# 405RGT6.net
KiCad netlist of a schematic drawn in Altium Designer
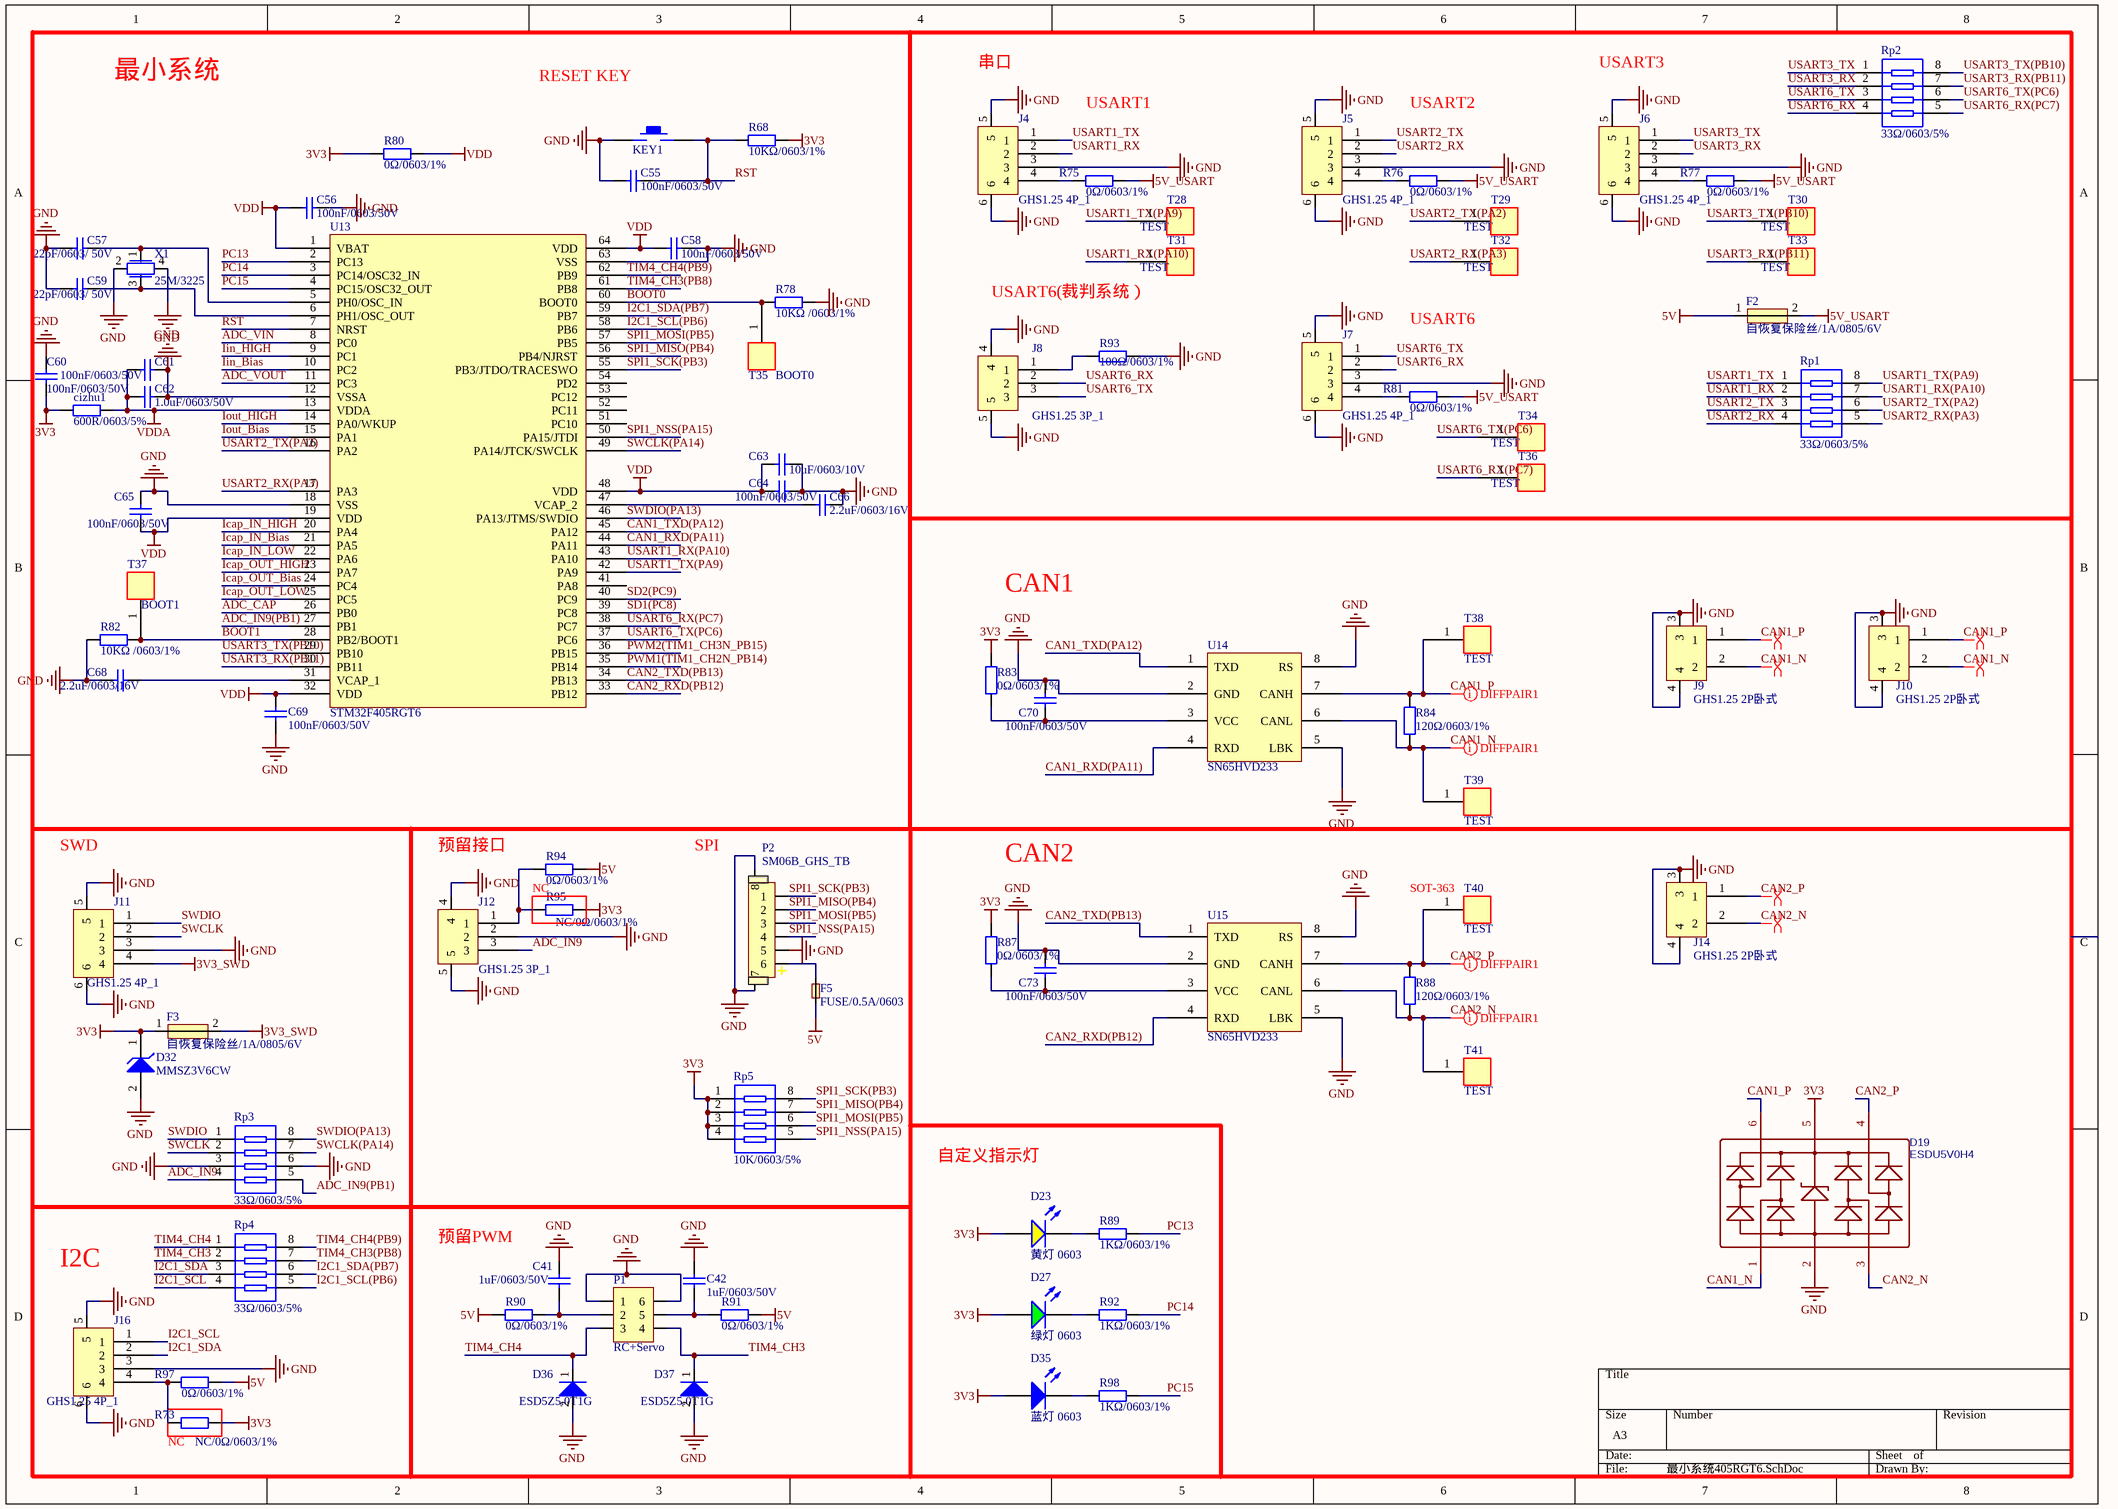
[diagram p0: 最小系统405RGT6.SchDoc]

(export (version "E")
  (design (tool "Eeschema 10.0.6"))
  (components
    (comp (ref "C41")
      (value "1uF/0603/50V")
      (footprint "0603_C")
      (description "贴片电容")
      (libsource (lib "Miscellaneous Devices LC") (part "0603 1uF (105) 10% 50V"))
    )
    (comp (ref "C42")
      (value "1uF/0603/50V")
      (footprint "0603_C")
      (description "贴片电容")
      (libsource (lib "Miscellaneous Devices LC") (part "0603 1uF (105) 10% 50V"))
    )
    (comp (ref "C55")
      (value "100nF/0603/50V")
      (footprint "0603_C")
      (description "贴片电容")
      (libsource (lib "Miscellaneous Devices LC") (part "0603 100nF (104) 10% 50V"))
    )
    (comp (ref "C56")
      (value "100nF/0603/50V")
      (footprint "0603_C")
      (description "贴片电容")
      (libsource (lib "Miscellaneous Devices LC") (part "0603 100nF (104) 10% 50V"))
    )
    (comp (ref "C57")
      (value "22pF/0603/ 50V")
      (footprint "0603_C")
      (description "贴片电容")
      (libsource (lib "Miscellaneous Devices LC") (part "0603 22pF (220) 5% 50V"))
    )
    (comp (ref "C58")
      (value "100nF/0603/50V")
      (footprint "0603_C")
      (description "贴片电容")
      (libsource (lib "Miscellaneous Devices LC") (part "0603 100nF (104) 10% 50V"))
    )
    (comp (ref "C59")
      (value "22pF/0603/ 50V")
      (footprint "0603_C")
      (description "贴片电容")
      (libsource (lib "Miscellaneous Devices LC") (part "0603 22pF (220) 5% 50V"))
    )
    (comp (ref "C60")
      (value "100nF/0603/50V")
      (footprint "0603_C")
      (description "贴片电容")
      (libsource (lib "Miscellaneous Devices LC") (part "0603 100nF (104) 10% 50V"))
    )
    (comp (ref "C61")
      (value "100nF/0603/50V")
      (footprint "0603_C")
      (description "贴片电容")
      (libsource (lib "Miscellaneous Devices LC") (part "0603 100nF (104) 10% 50V"))
    )
    (comp (ref "C62")
      (value "1.0uF/0603/50V")
      (footprint "0603_C")
      (description "贴片电容")
      (libsource (lib "Miscellaneous Devices LC") (part "0603 100nF (104) 10% 50V"))
    )
    (comp (ref "C63")
      (value "10uF/0603/10V")
      (footprint "0603_C")
      (description "贴片电容")
      (libsource (lib "Miscellaneous Devices LC") (part "0603 10uF (106) 10% 10V"))
    )
    (comp (ref "C64")
      (value "100nF/0603/50V")
      (footprint "0603_C")
      (description "贴片电容")
      (libsource (lib "Miscellaneous Devices LC") (part "0603 100nF (104) 10% 50V"))
    )
    (comp (ref "C65")
      (value "100nF/0603/50V")
      (footprint "0603_C")
      (description "贴片电容")
      (libsource (lib "Miscellaneous Devices LC") (part "0603 100nF (104) 10% 50V"))
    )
    (comp (ref "C66")
      (value "2.2uF/0603/16V")
      (footprint "0603_C")
      (description "贴片电容")
      (libsource (lib "Miscellaneous Devices LC") (part "0603 2.2uF (225) 10% 16V"))
    )
    (comp (ref "C68")
      (value "2.2uF/0603/16V")
      (footprint "0603_C")
      (description "贴片电容")
      (libsource (lib "Miscellaneous Devices LC") (part "0603 2.2uF (225) 10% 16V"))
    )
    (comp (ref "C69")
      (value "100nF/0603/50V")
      (footprint "0603_C")
      (description "贴片电容")
      (libsource (lib "Miscellaneous Devices LC") (part "0603 100nF (104) 10% 50V"))
    )
    (comp (ref "C70")
      (value "100nF/0603/50V")
      (footprint "0603_C")
      (description "贴片电容")
      (libsource (lib "Miscellaneous Devices LC") (part "0603 100nF (104) 10% 50V"))
    )
    (comp (ref "C73")
      (value "100nF/0603/50V")
      (footprint "0603_C")
      (description "贴片电容")
      (libsource (lib "Miscellaneous Devices LC") (part "0603 100nF (104) 10% 50V"))
    )
    (comp (ref "cizhu1")
      (value "600R/0603/5%")
      (footprint "0603_R")
      (description "贴片电阻")
      (libsource (lib "Miscellaneous Devices LC") (part "0603 100Ω (1000) 1%"))
    )
    (comp (ref "D19")
      (value "ESDU5V0H4")
      (footprint "SOT-23-6_L2.9-W1.6-P0.95-LS2.8-BR")
      (description "ESD")
      (fields (field (name "BOM_SUPPLIER PART") "C84837"))
      (libsource (lib "数字电源") (part "ESDU5V0H4"))
    )
    (comp (ref "D23")
      (value "黄灯 0603")
      (footprint "0603_LED_S1")
      (description "发光二极管")
      (libsource (lib "Miscellaneous Devices LC") (part "0603 黄灯"))
    )
    (comp (ref "D27")
      (value "绿灯 0603")
      (footprint "0603_LED_S1")
      (description "发光二极管")
      (libsource (lib "Miscellaneous Devices LC") (part "0603 绿灯"))
    )
    (comp (ref "D32")
      (value "MMSZ3V6CW")
      (footprint "SOD-123")
      (description "稳压二极管")
      (libsource (lib "数字电源") (part "LL-34 ZMM3V3"))
    )
    (comp (ref "D35")
      (value "蓝灯 0603")
      (footprint "0603_LED_S1")
      (description "发光二极管")
      (libsource (lib "Miscellaneous Devices LC") (part "0603 蓝灯"))
    )
    (comp (ref "D36")
      (value "ESD5Z5.0T1G")
      (footprint "SOD-523")
      (description "单向TVS")
      (libsource (lib "数字电源") (part "TVS_SOD-523"))
    )
    (comp (ref "D37")
      (value "ESD5Z5.0T1G")
      (footprint "SOD-523")
      (description "单向TVS")
      (libsource (lib "数字电源") (part "TVS_SOD-523"))
    )
    (comp (ref "F2")
      (value "自恢复保险丝/1A/0805/6V")
      (footprint "RobotLab_Common_Used:0805_R")
      (libsource (lib "RobotLab_Common_Used") (part "FUSE/0805"))
    )
    (comp (ref "F3")
      (value "自恢复保险丝/1A/0805/6V")
      (footprint "RobotLab_Common_Used:0805_R")
      (libsource (lib "RobotLab_Common_Used") (part "FUSE/0805"))
    )
    (comp (ref "F5")
      (value "FUSE/0.5A/0603")
      (footprint "0.5A/0603")
      (description "FUSE")
      (libsource (lib "数字电源") (part "FUSE/0.5A/0603"))
    )
    (comp (ref "J4")
      (value "GHS1.25 4P_1")
      (footprint "RobotLab_Common_Used:SM04B-GHS卧式")
      (description "卧式短边")
      (libsource (lib "RobotLab_Common_Used") (part "GHS1.25 4P_1"))
    )
    (comp (ref "J5")
      (value "GHS1.25 4P_1")
      (footprint "RobotLab_Common_Used:SM04B-GHS卧式")
      (description "卧式短边")
      (libsource (lib "RobotLab_Common_Used") (part "GHS1.25 4P_1"))
    )
    (comp (ref "J6")
      (value "GHS1.25 4P_1")
      (footprint "RobotLab_Common_Used:SM04B-GHS卧式")
      (description "卧式短边")
      (libsource (lib "RobotLab_Common_Used") (part "GHS1.25 4P_1"))
    )
    (comp (ref "J7")
      (value "GHS1.25 4P_1")
      (footprint "RobotLab_Common_Used:SM04B-GHS卧式")
      (description "卧式短边")
      (libsource (lib "RobotLab_Common_Used") (part "GHS1.25 4P_1"))
    )
    (comp (ref "J8")
      (value "GHS1.25 3P_1")
      (footprint "RobotLab_Common_Used:SM03B_GHS卧式")
      (description "卧式")
      (libsource (lib "RobotLab_Common_Used") (part "GHS1.25 3P_1"))
    )
    (comp (ref "J9")
      (value "GHS1.25 2P卧式")
      (footprint "RobotLab_Common_Used:SM02B-GHS卧式")
      (description "卧式")
      (libsource (lib "RobotLab_Common_Used") (part "GHS1.25 2P_1"))
    )
    (comp (ref "J10")
      (value "GHS1.25 2P卧式")
      (footprint "RobotLab_Common_Used:SM02B-GHS卧式")
      (description "卧式")
      (libsource (lib "RobotLab_Common_Used") (part "GHS1.25 2P_1"))
    )
    (comp (ref "J11")
      (value "GHS1.25 4P_1")
      (footprint "RobotLab_Common_Used:SM04B-GHS卧式")
      (description "卧式短边")
      (libsource (lib "RobotLab_Common_Used") (part "GHS1.25 4P_1"))
    )
    (comp (ref "J12")
      (value "GHS1.25 3P_1")
      (footprint "RobotLab_Common_Used:SM03B_GHS卧式")
      (description "卧式")
      (libsource (lib "RobotLab_Common_Used") (part "GHS1.25 3P_1"))
    )
    (comp (ref "J14")
      (value "GHS1.25 2P卧式")
      (footprint "RobotLab_Common_Used:SM02B-GHS卧式")
      (description "卧式")
      (libsource (lib "RobotLab_Common_Used") (part "GHS1.25 2P_1"))
    )
    (comp (ref "J16")
      (value "GHS1.25 4P_1")
      (footprint "RobotLab_Common_Used:SM04B-GHS卧式")
      (description "卧式短边")
      (libsource (lib "RobotLab_Common_Used") (part "GHS1.25 4P_1"))
    )
    (comp (ref "KEY1")
      (value "KEY")
      (footprint "RobotLab_Common_Used:SW-SMD1")
      (description "开关")
      (libsource (lib "RobotLab_Common_Used") (part "KEY"))
    )
    (comp (ref "P1") (value "RC+Servo") (footprint "RC+Servo") (libsource (lib "数字电源") (part "DBUS+Servo")))
    (comp (ref "P2")
      (value "SM06B_GHS_TB")
      (footprint "SM06B-GHS-TB")
      (libsource (lib "数字电源") (part "SM06B_GHS_TB"))
    )
    (comp (ref "R68")
      (value "10KΩ/0603/1%")
      (footprint "0603_R")
      (description "贴片电阻")
      (libsource (lib "Miscellaneous Devices LC") (part "0603 10KΩ (1002) 1%"))
    )
    (comp (ref "R73")
      (value "NC/0Ω/0603/1%")
      (footprint "0603_R")
      (description "贴片电阻")
      (libsource (lib "") (part "0603 0Ω (0R0) 1%_1"))
    )
    (comp (ref "R75")
      (value "0Ω/0603/1%")
      (footprint "0603_R")
      (description "贴片电阻")
      (libsource (lib "") (part "0603 0Ω (0R0) 1%_1"))
    )
    (comp (ref "R76")
      (value "0Ω/0603/1%")
      (footprint "0603_R")
      (description "贴片电阻")
      (libsource (lib "") (part "0603 0Ω (0R0) 1%_1"))
    )
    (comp (ref "R77")
      (value "0Ω/0603/1%")
      (footprint "0603_R")
      (description "贴片电阻")
      (libsource (lib "") (part "0603 0Ω (0R0) 1%_1"))
    )
    (comp (ref "R78")
      (value "10KΩ /0603/1%")
      (footprint "0603_R")
      (description "贴片电阻")
      (libsource (lib "Miscellaneous Devices LC") (part "0603 10KΩ (1002) 1%"))
    )
    (comp (ref "R80")
      (value "0Ω/0603/1%")
      (footprint "0603_R")
      (description "贴片电阻")
      (libsource (lib "") (part "0603 0Ω (0R0) 1%_1"))
    )
    (comp (ref "R81")
      (value "0Ω/0603/1%")
      (footprint "0603_R")
      (description "贴片电阻")
      (libsource (lib "") (part "0603 0Ω (0R0) 1%_1"))
    )
    (comp (ref "R82")
      (value "10KΩ /0603/1%")
      (footprint "0603_R")
      (description "贴片电阻")
      (libsource (lib "Miscellaneous Devices LC") (part "0603 10KΩ (1002) 1%"))
    )
    (comp (ref "R83")
      (value "0Ω/0603/1%")
      (footprint "0603_R")
      (description "贴片电阻")
      (libsource (lib "") (part "0603 0Ω (0R0) 1%_2"))
    )
    (comp (ref "R84")
      (value "120Ω/0603/1%")
      (footprint "0603_R")
      (description "贴片电阻")
      (libsource (lib "") (part "0603 100Ω (1000) 1%_1"))
    )
    (comp (ref "R87")
      (value "0Ω/0603/1%")
      (footprint "0603_R")
      (description "贴片电阻")
      (libsource (lib "") (part "0603 0Ω (0R0) 1%_2"))
    )
    (comp (ref "R88")
      (value "120Ω/0603/1%")
      (footprint "0603_R")
      (description "贴片电阻")
      (libsource (lib "") (part "0603 100Ω (1000) 1%_1"))
    )
    (comp (ref "R89")
      (value "1KΩ/0603/1%")
      (footprint "0603_R")
      (description "贴片电阻")
      (libsource (lib "Miscellaneous Devices LC") (part "0603 1KΩ (1001) 1%"))
    )
    (comp (ref "R90")
      (value "0Ω/0603/1%")
      (footprint "0603_R")
      (description "贴片电阻")
      (libsource (lib "Miscellaneous Devices LC") (part "0603 0Ω (0R0) 1%"))
    )
    (comp (ref "R91")
      (value "0Ω/0603/1%")
      (footprint "0603_R")
      (description "贴片电阻")
      (libsource (lib "Miscellaneous Devices LC") (part "0603 0Ω (0R0) 1%"))
    )
    (comp (ref "R92")
      (value "1KΩ/0603/1%")
      (footprint "0603_R")
      (description "贴片电阻")
      (libsource (lib "Miscellaneous Devices LC") (part "0603 1KΩ (1001) 1%"))
    )
    (comp (ref "R93")
      (value "100Ω/0603/1%")
      (footprint "0603_R")
      (description "贴片电阻")
      (libsource (lib "Miscellaneous Devices LC") (part "0603 100Ω (1000) 1%"))
    )
    (comp (ref "R94")
      (value "0Ω/0603/1%")
      (footprint "0603_R")
      (description "贴片电阻")
      (libsource (lib "Miscellaneous Devices LC") (part "0603 0Ω (0R0) 1%"))
    )
    (comp (ref "R95")
      (value "NC/0Ω/0603/1%")
      (footprint "0603_R")
      (description "贴片电阻")
      (libsource (lib "Miscellaneous Devices LC") (part "0603 0Ω (0R0) 1%"))
    )
    (comp (ref "R97")
      (value "0Ω/0603/1%")
      (footprint "0603_R")
      (description "贴片电阻")
      (libsource (lib "") (part "0603 0Ω (0R0) 1%_1"))
    )
    (comp (ref "R98")
      (value "1KΩ/0603/1%")
      (footprint "0603_R")
      (description "贴片电阻")
      (libsource (lib "Miscellaneous Devices LC") (part "0603 1KΩ (1001) 1%"))
    )
    (comp (ref "Rp1")
      (value "33Ω/0603/5%")
      (footprint "0603_Rx4")
      (description "贴片排阻")
      (libsource (lib "Miscellaneous Devices LC") (part "0603*4  10KΩ (103) 5%"))
    )
    (comp (ref "Rp2")
      (value "33Ω/0603/5%")
      (footprint "0603_Rx4")
      (description "贴片排阻")
      (libsource (lib "Miscellaneous Devices LC") (part "0603*4  10KΩ (103) 5%"))
    )
    (comp (ref "Rp3")
      (value "33Ω/0603/5%")
      (footprint "0603_Rx4")
      (description "贴片排阻")
      (libsource (lib "Miscellaneous Devices LC") (part "0603*4  10KΩ (103) 5%"))
    )
    (comp (ref "Rp4")
      (value "33Ω/0603/5%")
      (footprint "0603_Rx4")
      (description "贴片排阻")
      (libsource (lib "Miscellaneous Devices LC") (part "0603*4  10KΩ (103) 5%"))
    )
    (comp (ref "Rp5")
      (value "10K/0603/5%")
      (footprint "0603_Rx4")
      (description "贴片排阻")
      (libsource (lib "Miscellaneous Devices LC") (part "0603*4  10KΩ (103) 5%"))
    )
    (comp (ref "T28")
      (value "TEST")
      (footprint "测试点")
      (description "测试点")
      (libsource (lib "数字电源") (part "测试点"))
    )
    (comp (ref "T29")
      (value "TEST")
      (footprint "测试点")
      (description "测试点")
      (libsource (lib "数字电源") (part "测试点"))
    )
    (comp (ref "T30")
      (value "TEST")
      (footprint "测试点")
      (description "测试点")
      (libsource (lib "数字电源") (part "测试点"))
    )
    (comp (ref "T31")
      (value "TEST")
      (footprint "测试点")
      (description "测试点")
      (libsource (lib "数字电源") (part "测试点"))
    )
    (comp (ref "T32")
      (value "TEST")
      (footprint "测试点")
      (description "测试点")
      (libsource (lib "数字电源") (part "测试点"))
    )
    (comp (ref "T33")
      (value "TEST")
      (footprint "测试点")
      (description "测试点")
      (libsource (lib "数字电源") (part "测试点"))
    )
    (comp (ref "T34")
      (value "TEST")
      (footprint "测试点")
      (description "测试点")
      (libsource (lib "数字电源") (part "测试点"))
    )
    (comp (ref "T35")
      (value "BOOT0")
      (footprint "测试点")
      (description "测试点")
      (libsource (lib "") (part "测试点_1"))
    )
    (comp (ref "T36")
      (value "TEST")
      (footprint "测试点")
      (description "测试点")
      (libsource (lib "数字电源") (part "测试点"))
    )
    (comp (ref "T37")
      (value "BOOT1")
      (footprint "测试点")
      (description "测试点")
      (libsource (lib "") (part "测试点_2"))
    )
    (comp (ref "T38")
      (value "TEST")
      (footprint "测试点")
      (description "测试点")
      (libsource (lib "舵机控制Deus_v3.0") (part "测试点"))
    )
    (comp (ref "T39")
      (value "TEST")
      (footprint "测试点")
      (description "测试点")
      (libsource (lib "舵机控制Deus_v3.0") (part "测试点"))
    )
    (comp (ref "T40")
      (value "TEST")
      (footprint "测试点")
      (description "测试点")
      (libsource (lib "舵机控制Deus_v3.0") (part "测试点"))
    )
    (comp (ref "T41")
      (value "TEST")
      (footprint "测试点")
      (description "测试点")
      (libsource (lib "舵机控制Deus_v3.0") (part "测试点"))
    )
    (comp (ref "U13")
      (value "STM32F405RGT6")
      (footprint "LQFP64_M")
      (libsource (lib "数字电源") (part "STM32F405RGT6"))
    )
    (comp (ref "U14")
      (value "SN65HVD233")
      (footprint "RobotLab_Common_Used:SOIC-8_150mil")
      (libsource (lib "RobotLab_Common_Used") (part "SN65HVD233"))
    )
    (comp (ref "U15")
      (value "SN65HVD233")
      (footprint "RobotLab_Common_Used:SOIC-8_150mil")
      (libsource (lib "RobotLab_Common_Used") (part "SN65HVD233"))
    )
    (comp (ref "X1")
      (value "25M/3225")
      (footprint "RobotLab_Common_Used:SMD-3225_4P")
      (libsource (lib "RobotLab_Common_Used") (part "XTAL_4"))
    )
  )
  (nets
    (net (code "1") (name "/ADC_CAP") (class "Default")
      (node (ref "U13") (pin "26") (pinfunction "PB0_26") (pintype "passive"))
    )
    (net (code "2") (name "/ADC_IN9") (class "Default")
      (node (ref "J12") (pin "3") (pinfunction "3_3") (pintype "passive"))
      (node (ref "Rp3") (pin "4") (pinfunction "4_4") (pintype "passive"))
    )
    (net (code "3") (name "/ADC_IN9(PB1)") (class "Default")
      (node (ref "Rp3") (pin "5") (pinfunction "5_5") (pintype "passive"))
      (node (ref "U13") (pin "27") (pinfunction "PB1_27") (pintype "passive"))
    )
    (net (code "4") (name "/ADC_VIN") (class "Default")
      (node (ref "U13") (pin "8") (pinfunction "PC0_8") (pintype "passive"))
    )
    (net (code "5") (name "/ADC_VOUT") (class "Default")
      (node (ref "U13") (pin "11") (pinfunction "PC3_11") (pintype "passive"))
    )
    (net (code "6") (name "/BOOT0") (class "Default")
      (node (ref "R78") (pin "1") (pinfunction "1_1") (pintype "passive"))
      (node (ref "T35") (pin "1") (pinfunction "VIN_1") (pintype "passive"))
      (node (ref "U13") (pin "60") (pinfunction "BOOT0_60") (pintype "passive"))
    )
    (net (code "7") (name "/BOOT1") (class "Default")
      (node (ref "R82") (pin "2") (pinfunction "2_2") (pintype "passive"))
      (node (ref "T37") (pin "1") (pinfunction "VIN_1") (pintype "passive"))
      (node (ref "U13") (pin "28") (pinfunction "PB2/BOOT1_28") (pintype "passive"))
    )
    (net (code "8") (name "/CAN1_N") (class "Default")
      (node (ref "D19") (pin "1") (pinfunction "IO1_1") (pintype "passive"))
      (node (ref "J10") (pin "2") (pinfunction "2_2") (pintype "passive"))
      (node (ref "J9") (pin "2") (pinfunction "2_2") (pintype "passive"))
      (node (ref "R84") (pin "1") (pinfunction "1_1") (pintype "passive"))
      (node (ref "T39") (pin "1") (pinfunction "VIN_1") (pintype "passive"))
      (node (ref "U14") (pin "6") (pinfunction "CANL_6") (pintype "passive"))
    )
    (net (code "9") (name "/CAN1_P") (class "Default")
      (node (ref "D19") (pin "6") (pinfunction "IO2_6") (pintype "passive"))
      (node (ref "J10") (pin "1") (pinfunction "1_1") (pintype "passive"))
      (node (ref "J9") (pin "1") (pinfunction "1_1") (pintype "passive"))
      (node (ref "R84") (pin "2") (pinfunction "2_2") (pintype "passive"))
      (node (ref "T38") (pin "1") (pinfunction "VIN_1") (pintype "passive"))
      (node (ref "U14") (pin "7") (pinfunction "CANH_7") (pintype "passive"))
    )
    (net (code "10") (name "/CAN1_RXD(PA11)") (class "Default")
      (node (ref "U13") (pin "44") (pinfunction "PA11_44") (pintype "passive"))
      (node (ref "U14") (pin "4") (pinfunction "RXD_4") (pintype "passive"))
    )
    (net (code "11") (name "/CAN1_TXD(PA12)") (class "Default")
      (node (ref "U13") (pin "45") (pinfunction "PA12_45") (pintype "passive"))
      (node (ref "U14") (pin "1") (pinfunction "TXD_1") (pintype "passive"))
    )
    (net (code "12") (name "/CAN2_N") (class "Default")
      (node (ref "D19") (pin "3") (pinfunction "IO3_3") (pintype "passive"))
      (node (ref "J14") (pin "2") (pinfunction "2_2") (pintype "passive"))
      (node (ref "R88") (pin "1") (pinfunction "1_1") (pintype "passive"))
      (node (ref "T41") (pin "1") (pinfunction "VIN_1") (pintype "passive"))
      (node (ref "U15") (pin "6") (pinfunction "CANL_6") (pintype "passive"))
    )
    (net (code "13") (name "/CAN2_P") (class "Default")
      (node (ref "D19") (pin "4") (pinfunction "IO4_4") (pintype "passive"))
      (node (ref "J14") (pin "1") (pinfunction "1_1") (pintype "passive"))
      (node (ref "R88") (pin "2") (pinfunction "2_2") (pintype "passive"))
      (node (ref "T40") (pin "1") (pinfunction "VIN_1") (pintype "passive"))
      (node (ref "U15") (pin "7") (pinfunction "CANH_7") (pintype "passive"))
    )
    (net (code "14") (name "/CAN2_RXD(PB12)") (class "Default")
      (node (ref "U13") (pin "33") (pinfunction "PB12_33") (pintype "passive"))
      (node (ref "U15") (pin "4") (pinfunction "RXD_4") (pintype "passive"))
    )
    (net (code "15") (name "/CAN2_TXD(PB13)") (class "Default")
      (node (ref "U13") (pin "34") (pinfunction "PB13_34") (pintype "passive"))
      (node (ref "U15") (pin "1") (pinfunction "TXD_1") (pintype "passive"))
    )
    (net (code "16") (name "/I2C1_SCL") (class "Default")
      (node (ref "J16") (pin "1") (pinfunction "1_1") (pintype "passive"))
      (node (ref "Rp4") (pin "4") (pinfunction "4_4") (pintype "passive"))
    )
    (net (code "17") (name "/I2C1_SCL(PB6)") (class "Default")
      (node (ref "Rp4") (pin "5") (pinfunction "5_5") (pintype "passive"))
      (node (ref "U13") (pin "58") (pinfunction "PB6_58") (pintype "passive"))
    )
    (net (code "18") (name "/I2C1_SDA") (class "Default")
      (node (ref "J16") (pin "2") (pinfunction "2_2") (pintype "passive"))
      (node (ref "Rp4") (pin "3") (pinfunction "3_3") (pintype "passive"))
    )
    (net (code "19") (name "/I2C1_SDA(PB7)") (class "Default")
      (node (ref "Rp4") (pin "6") (pinfunction "6_6") (pintype "passive"))
      (node (ref "U13") (pin "59") (pinfunction "PB7_59") (pintype "passive"))
    )
    (net (code "20") (name "/Icap_IN_Bias") (class "Default")
      (node (ref "U13") (pin "21") (pinfunction "PA5_21") (pintype "passive"))
    )
    (net (code "21") (name "/Icap_IN_HIGH") (class "Default")
      (node (ref "U13") (pin "20") (pinfunction "PA4_20") (pintype "passive"))
    )
    (net (code "22") (name "/Icap_IN_LOW") (class "Default")
      (node (ref "U13") (pin "22") (pinfunction "PA6_22") (pintype "passive"))
    )
    (net (code "23") (name "/Icap_OUT_Bias") (class "Default")
      (node (ref "U13") (pin "24") (pinfunction "PC4_24") (pintype "passive"))
    )
    (net (code "24") (name "/Icap_OUT_HIGH") (class "Default")
      (node (ref "U13") (pin "23") (pinfunction "PA7_23") (pintype "passive"))
    )
    (net (code "25") (name "/Icap_OUT_LOW") (class "Default")
      (node (ref "U13") (pin "25") (pinfunction "PC5_25") (pintype "passive"))
    )
    (net (code "26") (name "/Iin_Bias") (class "Default")
      (node (ref "U13") (pin "10") (pinfunction "PC2_10") (pintype "passive"))
    )
    (net (code "27") (name "/Iin_HIGH") (class "Default")
      (node (ref "U13") (pin "9") (pinfunction "PC1_9") (pintype "passive"))
    )
    (net (code "28") (name "/Iout_Bias") (class "Default")
      (node (ref "U13") (pin "15") (pinfunction "PA1_15") (pintype "passive"))
    )
    (net (code "29") (name "/Iout_HIGH") (class "Default")
      (node (ref "U13") (pin "14") (pinfunction "PA0/WKUP_14") (pintype "passive"))
    )
    (net (code "30") (name "/PC13") (class "Default")
      (node (ref "R89") (pin "2") (pinfunction "2_2") (pintype "passive"))
      (node (ref "U13") (pin "2") (pinfunction "PC13_2") (pintype "passive"))
    )
    (net (code "31") (name "/PC14") (class "Default")
      (node (ref "R92") (pin "2") (pinfunction "2_2") (pintype "passive"))
      (node (ref "U13") (pin "3") (pinfunction "PC14/OSC32_IN_3") (pintype "passive"))
    )
    (net (code "32") (name "/PC15") (class "Default")
      (node (ref "R98") (pin "2") (pinfunction "2_2") (pintype "passive"))
      (node (ref "U13") (pin "4") (pinfunction "PC15/OSC32_OUT_4") (pintype "passive"))
    )
    (net (code "33") (name "/PWM1(TIM1_CH2N_PB14)") (class "Default")
      (node (ref "U13") (pin "35") (pinfunction "PB14_35") (pintype "passive"))
    )
    (net (code "34") (name "/PWM2(TIM1_CH3N_PB15)") (class "Default")
      (node (ref "U13") (pin "36") (pinfunction "PB15_36") (pintype "passive"))
    )
    (net (code "35") (name "/RST") (class "Default")
      (node (ref "C55") (pin "1") (pinfunction "1_1") (pintype "passive"))
      (node (ref "KEY1") (pin "2") (pinfunction "2_2") (pintype "passive"))
      (node (ref "R68") (pin "1") (pinfunction "1_1") (pintype "passive"))
      (node (ref "U13") (pin "7") (pinfunction "NRST_7") (pintype "passive"))
    )
    (net (code "36") (name "/SD1(PC8)") (class "Default")
      (node (ref "U13") (pin "39") (pinfunction "PC8_39") (pintype "passive"))
    )
    (net (code "37") (name "/SD2(PC9)") (class "Default")
      (node (ref "U13") (pin "40") (pinfunction "PC9_40") (pintype "passive"))
    )
    (net (code "38") (name "/SPI1_MISO(PB4)") (class "Default")
      (node (ref "P2") (pin "2") (pinfunction "2_2") (pintype "passive"))
      (node (ref "Rp5") (pin "7") (pinfunction "7_7") (pintype "passive"))
      (node (ref "U13") (pin "56") (pinfunction "PB4/NJRST_56") (pintype "passive"))
    )
    (net (code "39") (name "/SPI1_MOSI(PB5)") (class "Default")
      (node (ref "P2") (pin "3") (pinfunction "3_3") (pintype "passive"))
      (node (ref "Rp5") (pin "6") (pinfunction "6_6") (pintype "passive"))
      (node (ref "U13") (pin "57") (pinfunction "PB5_57") (pintype "passive"))
    )
    (net (code "40") (name "/SPI1_NSS(PA15)") (class "Default")
      (node (ref "P2") (pin "4") (pinfunction "4_4") (pintype "passive"))
      (node (ref "Rp5") (pin "5") (pinfunction "5_5") (pintype "passive"))
      (node (ref "U13") (pin "50") (pinfunction "PA15/JTDI_50") (pintype "passive"))
    )
    (net (code "41") (name "/SPI1_SCK(PB3)") (class "Default")
      (node (ref "P2") (pin "1") (pinfunction "1_1") (pintype "passive"))
      (node (ref "Rp5") (pin "8") (pinfunction "8_8") (pintype "passive"))
      (node (ref "U13") (pin "55") (pinfunction "PB3/JTDO/TRACESWO_55") (pintype "passive"))
    )
    (net (code "42") (name "/SWCLK") (class "Default")
      (node (ref "J11") (pin "2") (pinfunction "2_2") (pintype "passive"))
      (node (ref "Rp3") (pin "2") (pinfunction "2_2") (pintype "passive"))
    )
    (net (code "43") (name "/SWCLK(PA14)") (class "Default")
      (node (ref "Rp3") (pin "7") (pinfunction "7_7") (pintype "passive"))
      (node (ref "U13") (pin "49") (pinfunction "PA14/JTCK/SWCLK_49") (pintype "passive"))
    )
    (net (code "44") (name "/SWDIO") (class "Default")
      (node (ref "J11") (pin "1") (pinfunction "1_1") (pintype "passive"))
      (node (ref "Rp3") (pin "1") (pinfunction "1_1") (pintype "passive"))
    )
    (net (code "45") (name "/SWDIO(PA13)") (class "Default")
      (node (ref "Rp3") (pin "8") (pinfunction "8_8") (pintype "passive"))
      (node (ref "U13") (pin "46") (pinfunction "PA13/JTMS/SWDIO_46") (pintype "passive"))
    )
    (net (code "46") (name "/TIM4_CH3") (class "Default")
      (node (ref "D37") (pin "1") (pinfunction "K_1") (pintype "passive"))
      (node (ref "P1") (pin "4") (pinfunction "4_4") (pintype "passive"))
      (node (ref "Rp4") (pin "2") (pinfunction "2_2") (pintype "passive"))
    )
    (net (code "47") (name "/TIM4_CH3(PB8)") (class "Default")
      (node (ref "Rp4") (pin "7") (pinfunction "7_7") (pintype "passive"))
      (node (ref "U13") (pin "61") (pinfunction "PB8_61") (pintype "passive"))
    )
    (net (code "48") (name "/TIM4_CH4") (class "Default")
      (node (ref "D36") (pin "1") (pinfunction "K_1") (pintype "passive"))
      (node (ref "P1") (pin "3") (pinfunction "3_3") (pintype "passive"))
      (node (ref "Rp4") (pin "1") (pinfunction "1_1") (pintype "passive"))
    )
    (net (code "49") (name "/TIM4_CH4(PB9)") (class "Default")
      (node (ref "Rp4") (pin "8") (pinfunction "8_8") (pintype "passive"))
      (node (ref "U13") (pin "62") (pinfunction "PB9_62") (pintype "passive"))
    )
    (net (code "50") (name "/USART1_RX") (class "Default")
      (node (ref "J4") (pin "2") (pinfunction "2_2") (pintype "passive"))
      (node (ref "Rp1") (pin "2") (pinfunction "2_2") (pintype "passive"))
    )
    (net (code "51") (name "/USART1_RX(PA10)") (class "Default")
      (node (ref "Rp1") (pin "7") (pinfunction "7_7") (pintype "passive"))
      (node (ref "T31") (pin "1") (pinfunction "VIN_1") (pintype "passive"))
      (node (ref "U13") (pin "43") (pinfunction "PA10_43") (pintype "passive"))
    )
    (net (code "52") (name "/USART1_TX") (class "Default")
      (node (ref "J4") (pin "1") (pinfunction "1_1") (pintype "passive"))
      (node (ref "Rp1") (pin "1") (pinfunction "1_1") (pintype "passive"))
    )
    (net (code "53") (name "/USART1_TX(PA9)") (class "Default")
      (node (ref "Rp1") (pin "8") (pinfunction "8_8") (pintype "passive"))
      (node (ref "T28") (pin "1") (pinfunction "VIN_1") (pintype "passive"))
      (node (ref "U13") (pin "42") (pinfunction "PA9_42") (pintype "passive"))
    )
    (net (code "54") (name "/USART2_RX") (class "Default")
      (node (ref "J5") (pin "2") (pinfunction "2_2") (pintype "passive"))
      (node (ref "Rp1") (pin "4") (pinfunction "4_4") (pintype "passive"))
    )
    (net (code "55") (name "/USART2_RX(PA3)") (class "Default")
      (node (ref "Rp1") (pin "5") (pinfunction "5_5") (pintype "passive"))
      (node (ref "T32") (pin "1") (pinfunction "VIN_1") (pintype "passive"))
      (node (ref "U13") (pin "17") (pinfunction "PA3_17") (pintype "passive"))
    )
    (net (code "56") (name "/USART2_TX") (class "Default")
      (node (ref "J5") (pin "1") (pinfunction "1_1") (pintype "passive"))
      (node (ref "Rp1") (pin "3") (pinfunction "3_3") (pintype "passive"))
    )
    (net (code "57") (name "/USART2_TX(PA2)") (class "Default")
      (node (ref "Rp1") (pin "6") (pinfunction "6_6") (pintype "passive"))
      (node (ref "T29") (pin "1") (pinfunction "VIN_1") (pintype "passive"))
      (node (ref "U13") (pin "16") (pinfunction "PA2_16") (pintype "passive"))
    )
    (net (code "58") (name "/USART3_RX") (class "Default")
      (node (ref "J6") (pin "2") (pinfunction "2_2") (pintype "passive"))
      (node (ref "Rp2") (pin "2") (pinfunction "2_2") (pintype "passive"))
    )
    (net (code "59") (name "/USART3_RX(PB11)") (class "Default")
      (node (ref "Rp2") (pin "7") (pinfunction "7_7") (pintype "passive"))
      (node (ref "T33") (pin "1") (pinfunction "VIN_1") (pintype "passive"))
      (node (ref "U13") (pin "30") (pinfunction "PB11_30") (pintype "passive"))
    )
    (net (code "60") (name "/USART3_TX") (class "Default")
      (node (ref "J6") (pin "1") (pinfunction "1_1") (pintype "passive"))
      (node (ref "Rp2") (pin "1") (pinfunction "1_1") (pintype "passive"))
    )
    (net (code "61") (name "/USART3_TX(PB10)") (class "Default")
      (node (ref "Rp2") (pin "8") (pinfunction "8_8") (pintype "passive"))
      (node (ref "T30") (pin "1") (pinfunction "VIN_1") (pintype "passive"))
      (node (ref "U13") (pin "29") (pinfunction "PB10_29") (pintype "passive"))
    )
    (net (code "62") (name "/USART6_RX") (class "Default")
      (node (ref "J7") (pin "2") (pinfunction "2_2") (pintype "passive"))
      (node (ref "J8") (pin "2") (pinfunction "2_2") (pintype "passive"))
      (node (ref "Rp2") (pin "4") (pinfunction "4_4") (pintype "passive"))
    )
    (net (code "63") (name "/USART6_RX(PC7)") (class "Default")
      (node (ref "Rp2") (pin "5") (pinfunction "5_5") (pintype "passive"))
      (node (ref "T36") (pin "1") (pinfunction "VIN_1") (pintype "passive"))
      (node (ref "U13") (pin "38") (pinfunction "PC7_38") (pintype "passive"))
    )
    (net (code "64") (name "/USART6_TX") (class "Default")
      (node (ref "J7") (pin "1") (pinfunction "1_1") (pintype "passive"))
      (node (ref "J8") (pin "3") (pinfunction "3_3") (pintype "passive"))
      (node (ref "Rp2") (pin "3") (pinfunction "3_3") (pintype "passive"))
    )
    (net (code "65") (name "/USART6_TX(PC6)") (class "Default")
      (node (ref "Rp2") (pin "6") (pinfunction "6_6") (pintype "passive"))
      (node (ref "T34") (pin "1") (pinfunction "VIN_1") (pintype "passive"))
      (node (ref "U13") (pin "37") (pinfunction "PC6_37") (pintype "passive"))
    )
    (net (code "66") (name "3V3") (class "Default")
      (node (ref "C60") (pin "2") (pinfunction "2_2") (pintype "passive"))
      (node (ref "D19") (pin "5") (pinfunction "VCC_5") (pintype "passive"))
      (node (ref "D23") (pin "A") (pinfunction "A_A") (pintype "passive"))
      (node (ref "D27") (pin "A") (pinfunction "A_A") (pintype "passive"))
      (node (ref "D32") (pin "1") (pinfunction "K_1") (pintype "passive"))
      (node (ref "D35") (pin "A") (pinfunction "A_A") (pintype "passive"))
      (node (ref "F3") (pin "1") (pintype "passive"))
      (node (ref "R68") (pin "2") (pinfunction "2_2") (pintype "passive"))
      (node (ref "R73") (pin "2") (pinfunction "2_2") (pintype "passive"))
      (node (ref "R80") (pin "1") (pinfunction "1_1") (pintype "passive"))
      (node (ref "R83") (pin "2") (pinfunction "2_2") (pintype "passive"))
      (node (ref "R87") (pin "2") (pinfunction "2_2") (pintype "passive"))
      (node (ref "R95") (pin "1") (pinfunction "1_1") (pintype "passive"))
      (node (ref "Rp5") (pin "1") (pinfunction "1_1") (pintype "passive"))
      (node (ref "Rp5") (pin "2") (pinfunction "2_2") (pintype "passive"))
      (node (ref "Rp5") (pin "3") (pinfunction "3_3") (pintype "passive"))
      (node (ref "Rp5") (pin "4") (pinfunction "4_4") (pintype "passive"))
      (node (ref "cizhu1") (pin "1") (pinfunction "1_1") (pintype "passive"))
    )
    (net (code "67") (name "3V3_SWD") (class "Default")
      (node (ref "F3") (pin "2") (pintype "passive"))
      (node (ref "J11") (pin "4") (pinfunction "4_4") (pintype "passive"))
    )
    (net (code "68") (name "5V") (class "Default")
      (node (ref "F2") (pin "1") (pintype "passive"))
      (node (ref "F5") (pin "1") (pintype "passive"))
      (node (ref "R90") (pin "2") (pinfunction "2_2") (pintype "passive"))
      (node (ref "R91") (pin "1") (pinfunction "1_1") (pintype "passive"))
      (node (ref "R94") (pin "1") (pinfunction "1_1") (pintype "passive"))
      (node (ref "R97") (pin "2") (pinfunction "2_2") (pintype "passive"))
    )
    (net (code "69") (name "5V_USART") (class "Default")
      (node (ref "F2") (pin "2") (pintype "passive"))
      (node (ref "R75") (pin "2") (pinfunction "2_2") (pintype "passive"))
      (node (ref "R76") (pin "2") (pinfunction "2_2") (pintype "passive"))
      (node (ref "R77") (pin "2") (pinfunction "2_2") (pintype "passive"))
      (node (ref "R81") (pin "2") (pinfunction "2_2") (pintype "passive"))
    )
    (net (code "70") (name "GND") (class "Default")
      (node (ref "C41") (pin "2") (pinfunction "2_2") (pintype "passive"))
      (node (ref "C42") (pin "2") (pinfunction "2_2") (pintype "passive"))
      (node (ref "C55") (pin "2") (pinfunction "2_2") (pintype "passive"))
      (node (ref "C56") (pin "1") (pinfunction "1_1") (pintype "passive"))
      (node (ref "C57") (pin "1") (pinfunction "1_1") (pintype "passive"))
      (node (ref "C58") (pin "1") (pinfunction "1_1") (pintype "passive"))
      (node (ref "C59") (pin "1") (pinfunction "1_1") (pintype "passive"))
      (node (ref "C60") (pin "1") (pinfunction "1_1") (pintype "passive"))
      (node (ref "C61") (pin "1") (pinfunction "1_1") (pintype "passive"))
      (node (ref "C62") (pin "1") (pinfunction "1_1") (pintype "passive"))
      (node (ref "C63") (pin "2") (pinfunction "2_2") (pintype "passive"))
      (node (ref "C64") (pin "2") (pinfunction "2_2") (pintype "passive"))
      (node (ref "C65") (pin "1") (pinfunction "1_1") (pintype "passive"))
      (node (ref "C66") (pin "2") (pinfunction "2_2") (pintype "passive"))
      (node (ref "C68") (pin "1") (pinfunction "1_1") (pintype "passive"))
      (node (ref "C69") (pin "2") (pinfunction "2_2") (pintype "passive"))
      (node (ref "C70") (pin "2") (pinfunction "2_2") (pintype "passive"))
      (node (ref "C73") (pin "2") (pinfunction "2_2") (pintype "passive"))
      (node (ref "D19") (pin "2") (pinfunction "GND_2") (pintype "passive"))
      (node (ref "D32") (pin "2") (pinfunction "A_2") (pintype "passive"))
      (node (ref "D36") (pin "2") (pinfunction "A_2") (pintype "passive"))
      (node (ref "D37") (pin "2") (pinfunction "A_2") (pintype "passive"))
      (node (ref "J10") (pin "3") (pinfunction "3_3") (pintype "passive"))
      (node (ref "J10") (pin "4") (pinfunction "4_4") (pintype "passive"))
      (node (ref "J11") (pin "3") (pinfunction "3_3") (pintype "passive"))
      (node (ref "J11") (pin "5") (pinfunction "5_5") (pintype "passive"))
      (node (ref "J11") (pin "6") (pinfunction "6_6") (pintype "passive"))
      (node (ref "J12") (pin "2") (pinfunction "2_2") (pintype "passive"))
      (node (ref "J12") (pin "4") (pinfunction "4_4") (pintype "passive"))
      (node (ref "J12") (pin "5") (pinfunction "5_5") (pintype "passive"))
      (node (ref "J14") (pin "3") (pinfunction "3_3") (pintype "passive"))
      (node (ref "J14") (pin "4") (pinfunction "4_4") (pintype "passive"))
      (node (ref "J16") (pin "3") (pinfunction "3_3") (pintype "passive"))
      (node (ref "J16") (pin "5") (pinfunction "5_5") (pintype "passive"))
      (node (ref "J16") (pin "6") (pinfunction "6_6") (pintype "passive"))
      (node (ref "J4") (pin "3") (pinfunction "3_3") (pintype "passive"))
      (node (ref "J4") (pin "5") (pinfunction "5_5") (pintype "passive"))
      (node (ref "J4") (pin "6") (pinfunction "6_6") (pintype "passive"))
      (node (ref "J5") (pin "3") (pinfunction "3_3") (pintype "passive"))
      (node (ref "J5") (pin "5") (pinfunction "5_5") (pintype "passive"))
      (node (ref "J5") (pin "6") (pinfunction "6_6") (pintype "passive"))
      (node (ref "J6") (pin "3") (pinfunction "3_3") (pintype "passive"))
      (node (ref "J6") (pin "5") (pinfunction "5_5") (pintype "passive"))
      (node (ref "J6") (pin "6") (pinfunction "6_6") (pintype "passive"))
      (node (ref "J7") (pin "3") (pinfunction "3_3") (pintype "passive"))
      (node (ref "J7") (pin "5") (pinfunction "5_5") (pintype "passive"))
      (node (ref "J7") (pin "6") (pinfunction "6_6") (pintype "passive"))
      (node (ref "J8") (pin "4") (pinfunction "4_4") (pintype "passive"))
      (node (ref "J8") (pin "5") (pinfunction "5_5") (pintype "passive"))
      (node (ref "J9") (pin "3") (pinfunction "3_3") (pintype "passive"))
      (node (ref "J9") (pin "4") (pinfunction "4_4") (pintype "passive"))
      (node (ref "KEY1") (pin "1") (pinfunction "1_1") (pintype "passive"))
      (node (ref "P1") (pin "1") (pinfunction "1_1") (pintype "passive"))
      (node (ref "P1") (pin "6") (pinfunction "6_6") (pintype "passive"))
      (node (ref "P2") (pin "5") (pinfunction "5_5") (pintype "passive"))
      (node (ref "P2") (pin "7") (pinfunction "7_7") (pintype "passive"))
      (node (ref "P2") (pin "8") (pinfunction "8_8") (pintype "passive"))
      (node (ref "R78") (pin "2") (pinfunction "2_2") (pintype "passive"))
      (node (ref "R82") (pin "1") (pinfunction "1_1") (pintype "passive"))
      (node (ref "R93") (pin "2") (pinfunction "2_2") (pintype "passive"))
      (node (ref "Rp3") (pin "3") (pinfunction "3_3") (pintype "passive"))
      (node (ref "Rp3") (pin "6") (pinfunction "6_6") (pintype "passive"))
      (node (ref "U13") (pin "12") (pinfunction "VSSA_12") (pintype "power_in"))
      (node (ref "U13") (pin "18") (pinfunction "VSS_18") (pintype "power_in"))
      (node (ref "U13") (pin "63") (pinfunction "VSS_63") (pintype "power_in"))
      (node (ref "U14") (pin "2") (pinfunction "GND_2") (pintype "passive"))
      (node (ref "U14") (pin "5") (pinfunction "LBK_5") (pintype "passive"))
      (node (ref "U14") (pin "8") (pinfunction "RS_8") (pintype "passive"))
      (node (ref "U15") (pin "2") (pinfunction "GND_2") (pintype "passive"))
      (node (ref "U15") (pin "5") (pinfunction "LBK_5") (pintype "passive"))
      (node (ref "U15") (pin "8") (pinfunction "RS_8") (pintype "passive"))
      (node (ref "X1") (pin "2") (pinfunction "GND_2") (pintype "passive"))
      (node (ref "X1") (pin "4") (pinfunction "GND_4") (pintype "passive"))
    )
    (net (code "71") (name "Net-(C41-Pad1)") (class "Default")
      (node (ref "C41") (pin "1") (pinfunction "1_1") (pintype "passive"))
      (node (ref "P1") (pin "2") (pinfunction "2_2") (pintype "passive"))
      (node (ref "R90") (pin "1") (pinfunction "1_1") (pintype "passive"))
    )
    (net (code "72") (name "Net-(C42-Pad1)") (class "Default")
      (node (ref "C42") (pin "1") (pinfunction "1_1") (pintype "passive"))
      (node (ref "P1") (pin "5") (pinfunction "5_5") (pintype "passive"))
      (node (ref "R91") (pin "2") (pinfunction "2_2") (pintype "passive"))
    )
    (net (code "73") (name "Net-(D23-PadK)") (class "Default")
      (node (ref "D23") (pin "K") (pinfunction "K_K") (pintype "passive"))
      (node (ref "R89") (pin "1") (pinfunction "1_1") (pintype "passive"))
    )
    (net (code "74") (name "Net-(D27-PadK)") (class "Default")
      (node (ref "D27") (pin "K") (pinfunction "K_K") (pintype "passive"))
      (node (ref "R92") (pin "1") (pinfunction "1_1") (pintype "passive"))
    )
    (net (code "75") (name "Net-(D35-PadK)") (class "Default")
      (node (ref "D35") (pin "K") (pinfunction "K_K") (pintype "passive"))
      (node (ref "R98") (pin "1") (pinfunction "1_1") (pintype "passive"))
    )
    (net (code "76") (name "Net-(F5-Pad2)") (class "Default")
      (node (ref "F5") (pin "2") (pintype "passive"))
      (node (ref "P2") (pin "6") (pinfunction "6_6") (pintype "passive"))
    )
    (net (code "77") (name "Net-(J4-Pad4)") (class "Default")
      (node (ref "J4") (pin "4") (pinfunction "4_4") (pintype "passive"))
      (node (ref "R75") (pin "1") (pinfunction "1_1") (pintype "passive"))
    )
    (net (code "78") (name "Net-(J5-Pad4)") (class "Default")
      (node (ref "J5") (pin "4") (pinfunction "4_4") (pintype "passive"))
      (node (ref "R76") (pin "1") (pinfunction "1_1") (pintype "passive"))
    )
    (net (code "79") (name "Net-(J6-Pad4)") (class "Default")
      (node (ref "J6") (pin "4") (pinfunction "4_4") (pintype "passive"))
      (node (ref "R77") (pin "1") (pinfunction "1_1") (pintype "passive"))
    )
    (net (code "80") (name "Net-(J7-Pad4)") (class "Default")
      (node (ref "J7") (pin "4") (pinfunction "4_4") (pintype "passive"))
      (node (ref "R81") (pin "1") (pinfunction "1_1") (pintype "passive"))
    )
    (net (code "81") (name "Net-(J8-Pad1)") (class "Default")
      (node (ref "J8") (pin "1") (pinfunction "1_1") (pintype "passive"))
      (node (ref "R93") (pin "1") (pinfunction "1_1") (pintype "passive"))
    )
    (net (code "82") (name "Net-(J12-Pad1)") (class "Default")
      (node (ref "J12") (pin "1") (pinfunction "1_1") (pintype "passive"))
      (node (ref "R94") (pin "2") (pinfunction "2_2") (pintype "passive"))
      (node (ref "R95") (pin "2") (pinfunction "2_2") (pintype "passive"))
    )
    (net (code "83") (name "Net-(J16-Pad4)") (class "Default")
      (node (ref "J16") (pin "4") (pinfunction "4_4") (pintype "passive"))
      (node (ref "R73") (pin "1") (pinfunction "1_1") (pintype "passive"))
      (node (ref "R97") (pin "1") (pinfunction "1_1") (pintype "passive"))
    )
    (net (code "84") (name "Net-(U13-PH0{slash}OSC_IN)") (class "Default")
      (node (ref "C57") (pin "2") (pinfunction "2_2") (pintype "passive"))
      (node (ref "U13") (pin "5") (pinfunction "PH0/OSC_IN_5") (pintype "passive"))
      (node (ref "X1") (pin "1") (pinfunction "OUT_1") (pintype "passive"))
    )
    (net (code "85") (name "Net-(U13-PH1{slash}OSC_OUT)") (class "Default")
      (node (ref "C59") (pin "2") (pinfunction "2_2") (pintype "passive"))
      (node (ref "U13") (pin "6") (pinfunction "PH1/OSC_OUT_6") (pintype "passive"))
      (node (ref "X1") (pin "3") (pinfunction "OUT_3") (pintype "passive"))
    )
    (net (code "86") (name "Net-(U13-VCAP_1)") (class "Default")
      (node (ref "C68") (pin "2") (pinfunction "2_2") (pintype "passive"))
      (node (ref "U13") (pin "31") (pinfunction "VCAP_1_31") (pintype "passive"))
    )
    (net (code "87") (name "Net-(U13-VCAP_2)") (class "Default")
      (node (ref "C66") (pin "1") (pinfunction "1_1") (pintype "passive"))
      (node (ref "U13") (pin "47") (pinfunction "VCAP_2_47") (pintype "passive"))
    )
    (net (code "88") (name "Net-(U14-VCC)") (class "Default")
      (node (ref "C70") (pin "1") (pinfunction "1_1") (pintype "passive"))
      (node (ref "R83") (pin "1") (pinfunction "1_1") (pintype "passive"))
      (node (ref "U14") (pin "3") (pinfunction "VCC_3") (pintype "passive"))
    )
    (net (code "89") (name "Net-(U15-VCC)") (class "Default")
      (node (ref "C73") (pin "1") (pinfunction "1_1") (pintype "passive"))
      (node (ref "R87") (pin "1") (pinfunction "1_1") (pintype "passive"))
      (node (ref "U15") (pin "3") (pinfunction "VCC_3") (pintype "passive"))
    )
    (net (code "90") (name "VDD") (class "Default")
      (node (ref "C56") (pin "2") (pinfunction "2_2") (pintype "passive"))
      (node (ref "C58") (pin "2") (pinfunction "2_2") (pintype "passive"))
      (node (ref "C63") (pin "1") (pinfunction "1_1") (pintype "passive"))
      (node (ref "C64") (pin "1") (pinfunction "1_1") (pintype "passive"))
      (node (ref "C65") (pin "2") (pinfunction "2_2") (pintype "passive"))
      (node (ref "C69") (pin "1") (pinfunction "1_1") (pintype "passive"))
      (node (ref "R80") (pin "2") (pinfunction "2_2") (pintype "passive"))
      (node (ref "U13") (pin "1") (pinfunction "VBAT_1") (pintype "power_in"))
      (node (ref "U13") (pin "19") (pinfunction "VDD_19") (pintype "power_in"))
      (node (ref "U13") (pin "32") (pinfunction "VDD_32") (pintype "power_in"))
      (node (ref "U13") (pin "48") (pinfunction "VDD_48") (pintype "power_in"))
      (node (ref "U13") (pin "64") (pinfunction "VDD_64") (pintype "power_in"))
    )
    (net (code "91") (name "VDDA") (class "Default")
      (node (ref "C61") (pin "2") (pinfunction "2_2") (pintype "passive"))
      (node (ref "C62") (pin "2") (pinfunction "2_2") (pintype "passive"))
      (node (ref "U13") (pin "13") (pinfunction "VDDA_13") (pintype "power_in"))
      (node (ref "cizhu1") (pin "2") (pinfunction "2_2") (pintype "passive"))
    )
    (net (code "92") (name "unconnected-(U13-PA8-Pad41)") (class "Default")
      (node (ref "U13") (pin "41") (pinfunction "PA8_41") (pintype "passive"))
    )
    (net (code "93") (name "unconnected-(U13-PC10-Pad51)") (class "Default")
      (node (ref "U13") (pin "51") (pinfunction "PC10_51") (pintype "passive"))
    )
    (net (code "94") (name "unconnected-(U13-PC11-Pad52)") (class "Default")
      (node (ref "U13") (pin "52") (pinfunction "PC11_52") (pintype "passive"))
    )
    (net (code "95") (name "unconnected-(U13-PC12-Pad53)") (class "Default")
      (node (ref "U13") (pin "53") (pinfunction "PC12_53") (pintype "passive"))
    )
    (net (code "96") (name "unconnected-(U13-PD2-Pad54)") (class "Default")
      (node (ref "U13") (pin "54") (pinfunction "PD2_54") (pintype "passive"))
    )
  )
)
